# RPI_HAT_AMP_TAS5756_01.net
KiCad netlist of a schematic drawn in Altium Designer
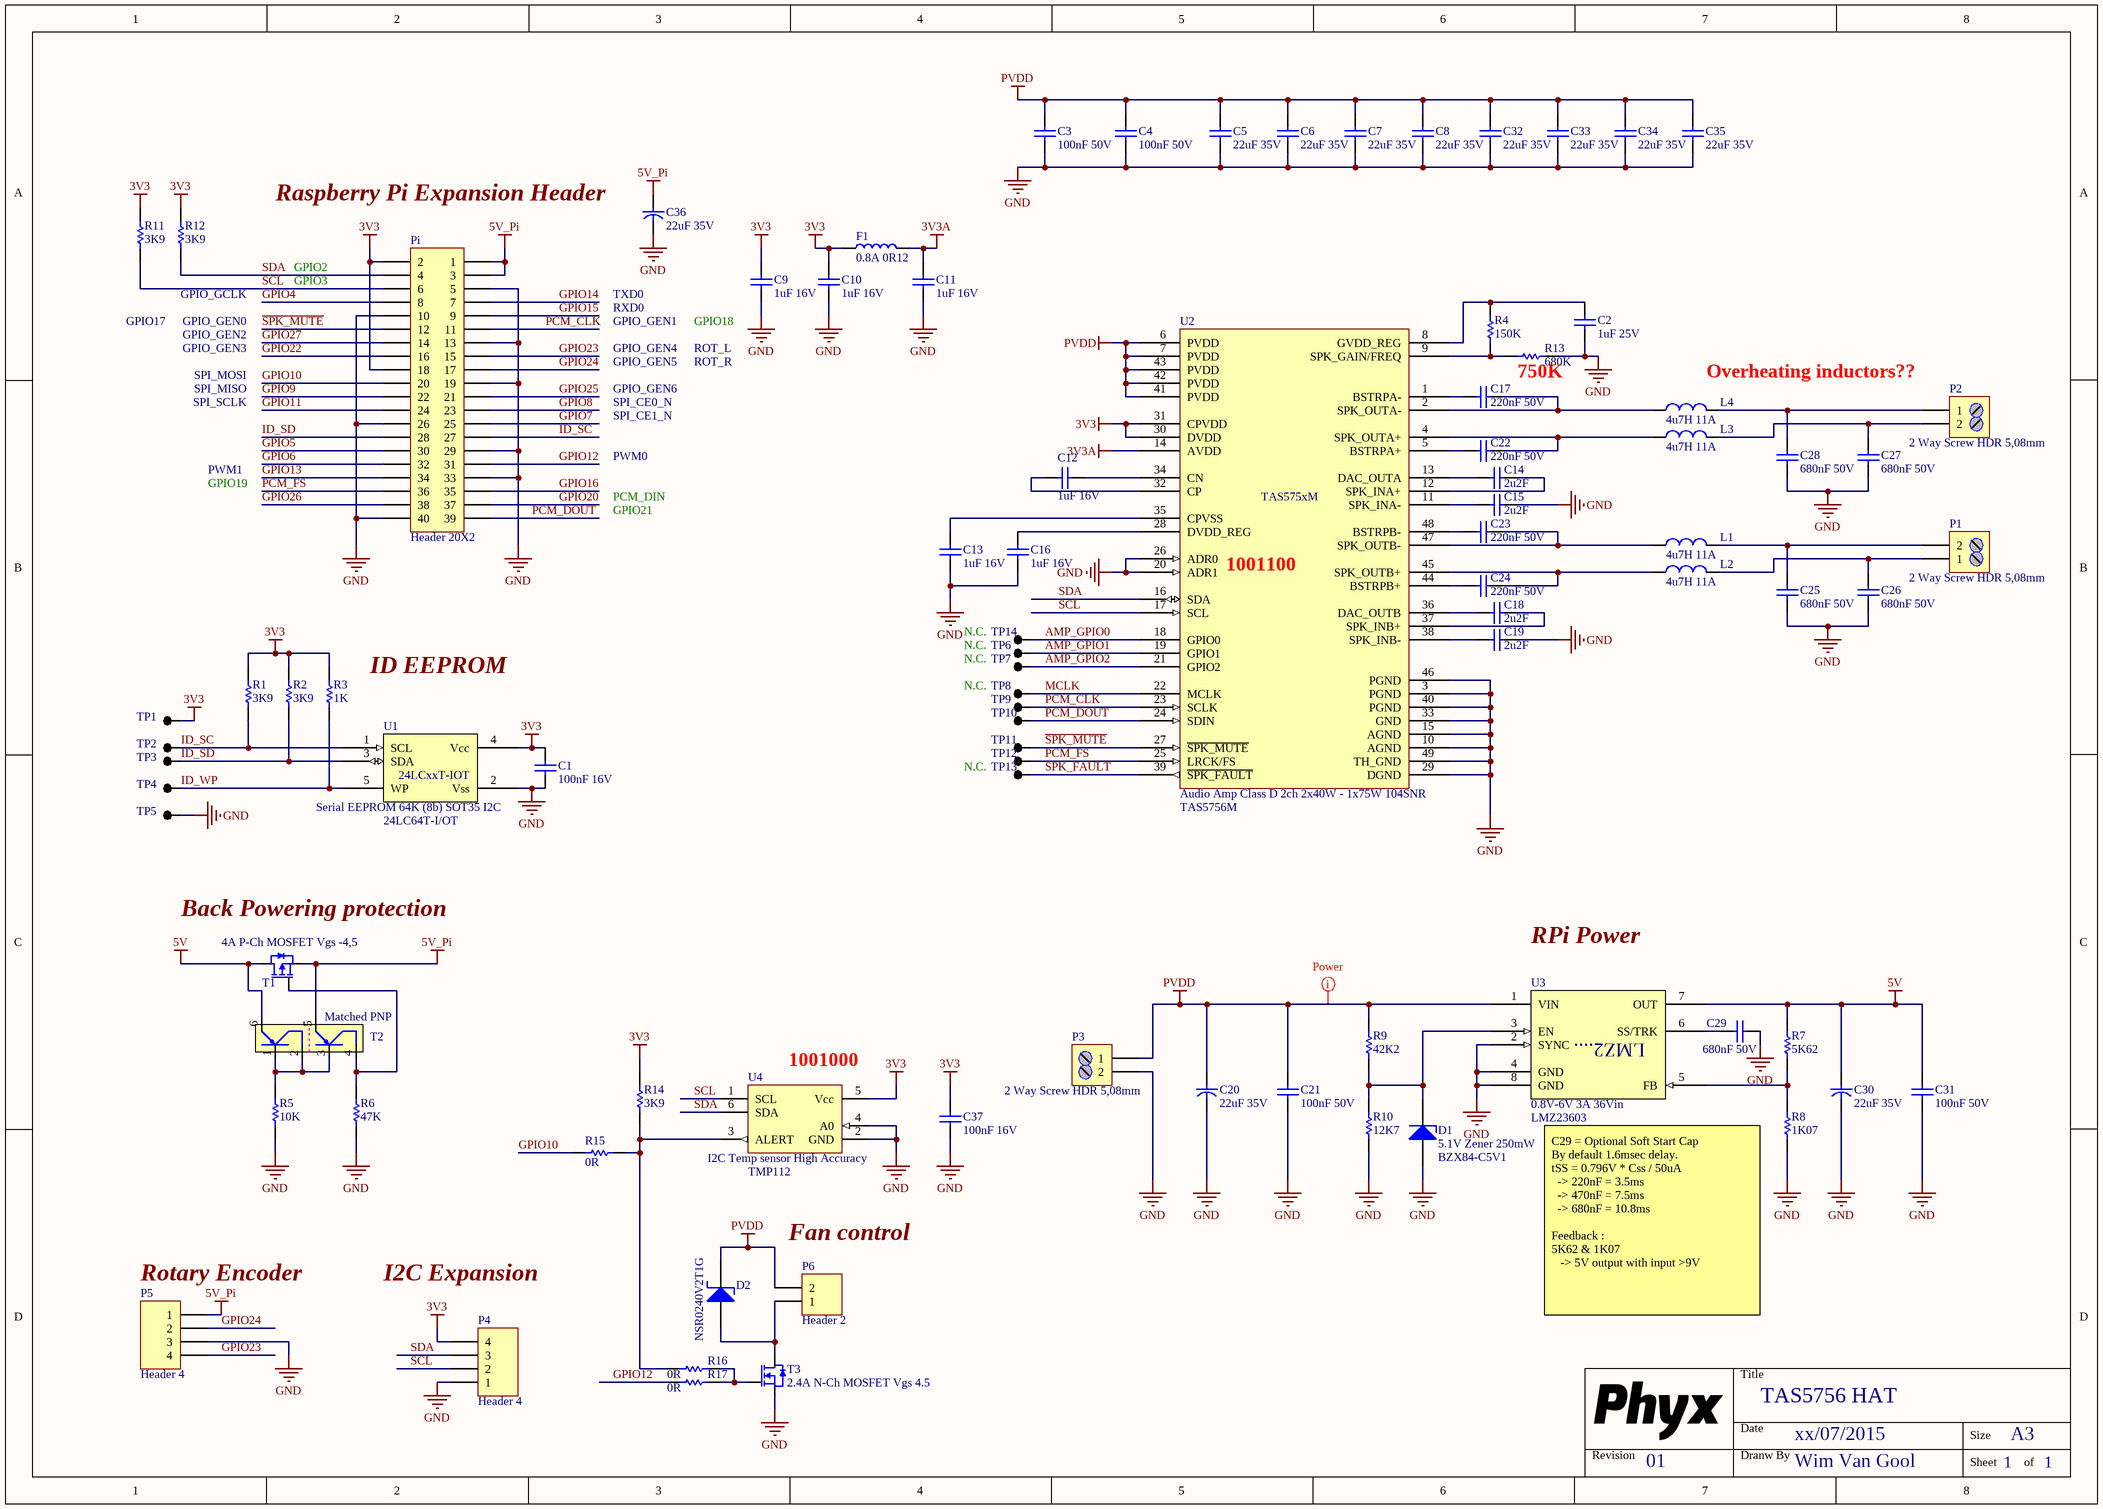
[diagram p0: RPI_HAT_AMP_TAS5756_01.SchDoc]

(export (version "E")
  (design (tool "Eeschema 10.0.6"))
  (components
    (comp (ref "C1")
      (value "100nF 16V")
      (footprint "C0603")
      (description "Capacitor Ceramic")
      (fields (field (name "Comment") "CAP_CERAMIC"))
      (libsource (lib "Phyx_Components") (part "CAP_CERAMIC"))
    )
    (comp (ref "C2")
      (value "1uF 25V")
      (footprint "C0805")
      (description "Capacitor Ceramic")
      (fields (field (name "Comment") "CAP_CERAMIC"))
      (libsource (lib "Phyx_Components") (part "CAP_CERAMIC"))
    )
    (comp (ref "C3")
      (value "100nF 50V")
      (footprint "C0805")
      (description "Capacitor Ceramic")
      (fields (field (name "Comment") "CAP_CERAMIC"))
      (libsource (lib "Phyx_Components") (part "CAP_CERAMIC"))
    )
    (comp (ref "C4")
      (value "100nF 50V")
      (footprint "C0805")
      (description "Capacitor Ceramic")
      (fields (field (name "Comment") "CAP_CERAMIC"))
      (libsource (lib "Phyx_Components") (part "CAP_CERAMIC"))
    )
    (comp (ref "C5")
      (value "22uF 35V")
      (footprint "C1206")
      (description "Capacitor Ceramic")
      (fields (field (name "Comment") "CAP_CERAMIC"))
      (libsource (lib "Phyx_Components") (part "CAP_CERAMIC"))
    )
    (comp (ref "C6")
      (value "22uF 35V")
      (footprint "C1206")
      (description "Capacitor Ceramic")
      (fields (field (name "Comment") "CAP_CERAMIC"))
      (libsource (lib "Phyx_Components") (part "CAP_CERAMIC"))
    )
    (comp (ref "C7")
      (value "22uF 35V")
      (footprint "C1206")
      (description "Capacitor Ceramic")
      (fields (field (name "Comment") "CAP_CERAMIC"))
      (libsource (lib "Phyx_Components") (part "CAP_CERAMIC"))
    )
    (comp (ref "C8")
      (value "22uF 35V")
      (footprint "C1206")
      (description "Capacitor Ceramic")
      (fields (field (name "Comment") "CAP_CERAMIC"))
      (libsource (lib "Phyx_Components") (part "CAP_CERAMIC"))
    )
    (comp (ref "C9")
      (value "1uF 16V")
      (footprint "C0603")
      (description "Capacitor Ceramic")
      (fields (field (name "Comment") "CAP_CERAMIC"))
      (libsource (lib "Phyx_Components") (part "CAP_CERAMIC"))
    )
    (comp (ref "C10")
      (value "1uF 16V")
      (footprint "C0603")
      (description "Capacitor Ceramic")
      (fields (field (name "Comment") "CAP_CERAMIC"))
      (libsource (lib "Phyx_Components") (part "CAP_CERAMIC"))
    )
    (comp (ref "C11")
      (value "1uF 16V")
      (footprint "C0603")
      (description "Capacitor Ceramic")
      (fields (field (name "Comment") "CAP_CERAMIC"))
      (libsource (lib "Phyx_Components") (part "CAP_CERAMIC"))
    )
    (comp (ref "C12")
      (value "1uF 16V")
      (footprint "C0603")
      (description "Capacitor Ceramic")
      (fields (field (name "Comment") "CAP_CERAMIC"))
      (libsource (lib "Phyx_Components") (part "CAP_CERAMIC"))
    )
    (comp (ref "C13")
      (value "1uF 16V")
      (footprint "C0603")
      (description "Capacitor Ceramic")
      (fields (field (name "Comment") "CAP_CERAMIC"))
      (libsource (lib "Phyx_Components") (part "CAP_CERAMIC"))
    )
    (comp (ref "C14")
      (value "2u2F")
      (footprint "C0805")
      (description "Capacitor Ceramic")
      (fields (field (name "Comment") "CAP_CERAMIC"))
      (libsource (lib "Phyx_Components") (part "CAP_CERAMIC"))
    )
    (comp (ref "C15")
      (value "2u2F")
      (footprint "C0805")
      (description "Capacitor Ceramic")
      (fields (field (name "Comment") "CAP_CERAMIC"))
      (libsource (lib "Phyx_Components") (part "CAP_CERAMIC"))
    )
    (comp (ref "C16")
      (value "1uF 16V")
      (footprint "C0603")
      (description "Capacitor Ceramic")
      (fields (field (name "Comment") "CAP_CERAMIC"))
      (libsource (lib "Phyx_Components") (part "CAP_CERAMIC"))
    )
    (comp (ref "C17")
      (value "220nF 50V")
      (footprint "C0805")
      (description "Capacitor Ceramic")
      (fields (field (name "Comment") "CAP_CERAMIC"))
      (libsource (lib "Phyx_Components") (part "CAP_CERAMIC"))
    )
    (comp (ref "C18")
      (value "2u2F")
      (footprint "C0805")
      (description "Capacitor Ceramic")
      (fields (field (name "Comment") "CAP_CERAMIC"))
      (libsource (lib "Phyx_Components") (part "CAP_CERAMIC"))
    )
    (comp (ref "C19")
      (value "2u2F")
      (footprint "C0805")
      (description "Capacitor Ceramic")
      (fields (field (name "Comment") "CAP_CERAMIC"))
      (libsource (lib "Phyx_Components") (part "CAP_CERAMIC"))
    )
    (comp (ref "C20")
      (value "22uF 35V")
      (footprint "C6.6x5.4")
      (description "Capacitor electrolyt")
      (fields (field (name "Comment") "CAP_POL"))
      (libsource (lib "Phyx_Components") (part "CAP_POL"))
    )
    (comp (ref "C21")
      (value "100nF 50V")
      (footprint "C0805")
      (description "Capacitor Ceramic")
      (fields (field (name "Comment") "CAP_CERAMIC"))
      (libsource (lib "Phyx_Components") (part "CAP_CERAMIC"))
    )
    (comp (ref "C22")
      (value "220nF 50V")
      (footprint "C0805")
      (description "Capacitor Ceramic")
      (fields (field (name "Comment") "CAP_CERAMIC"))
      (libsource (lib "Phyx_Components") (part "CAP_CERAMIC"))
    )
    (comp (ref "C23")
      (value "220nF 50V")
      (footprint "C0805")
      (description "Capacitor Ceramic")
      (fields (field (name "Comment") "CAP_CERAMIC"))
      (libsource (lib "Phyx_Components") (part "CAP_CERAMIC"))
    )
    (comp (ref "C24")
      (value "220nF 50V")
      (footprint "C0805")
      (description "Capacitor Ceramic")
      (fields (field (name "Comment") "CAP_CERAMIC"))
      (libsource (lib "Phyx_Components") (part "CAP_CERAMIC"))
    )
    (comp (ref "C25")
      (value "680nF 50V")
      (footprint "C0805")
      (description "Capacitor Ceramic")
      (fields (field (name "Comment") "CAP_CERAMIC"))
      (libsource (lib "Phyx_Components") (part "CAP_CERAMIC"))
    )
    (comp (ref "C26")
      (value "680nF 50V")
      (footprint "C0805")
      (description "Capacitor Ceramic")
      (fields (field (name "Comment") "CAP_CERAMIC"))
      (libsource (lib "Phyx_Components") (part "CAP_CERAMIC"))
    )
    (comp (ref "C27")
      (value "680nF 50V")
      (footprint "C0805")
      (description "Capacitor Ceramic")
      (fields (field (name "Comment") "CAP_CERAMIC"))
      (libsource (lib "Phyx_Components") (part "CAP_CERAMIC"))
    )
    (comp (ref "C28")
      (value "680nF 50V")
      (footprint "C0805")
      (description "Capacitor Ceramic")
      (fields (field (name "Comment") "CAP_CERAMIC"))
      (libsource (lib "Phyx_Components") (part "CAP_CERAMIC"))
    )
    (comp (ref "C29")
      (value "680nF 50V")
      (footprint "C0805")
      (description "Capacitor Ceramic")
      (fields (field (name "Comment") "CAP_CERAMIC"))
      (libsource (lib "Phyx_Components") (part "CAP_CERAMIC"))
    )
    (comp (ref "C30")
      (value "22uF 35V")
      (footprint "C6.6x5.4")
      (description "Capacitor electrolyt")
      (fields (field (name "Comment") "CAP_POL"))
      (libsource (lib "Phyx_Components") (part "CAP_POL"))
    )
    (comp (ref "C31")
      (value "100nF 50V")
      (footprint "C0805")
      (description "Capacitor Ceramic")
      (fields (field (name "Comment") "CAP_CERAMIC"))
      (libsource (lib "Phyx_Components") (part "CAP_CERAMIC"))
    )
    (comp (ref "C32")
      (value "22uF 35V")
      (footprint "C1206")
      (description "Capacitor Ceramic")
      (fields (field (name "Comment") "CAP_CERAMIC"))
      (libsource (lib "Phyx_Components") (part "CAP_CERAMIC"))
    )
    (comp (ref "C33")
      (value "22uF 35V")
      (footprint "C1206")
      (description "Capacitor Ceramic")
      (fields (field (name "Comment") "CAP_CERAMIC"))
      (libsource (lib "Phyx_Components") (part "CAP_CERAMIC"))
    )
    (comp (ref "C34")
      (value "22uF 35V")
      (footprint "C1206")
      (description "Capacitor Ceramic")
      (fields (field (name "Comment") "CAP_CERAMIC"))
      (libsource (lib "Phyx_Components") (part "CAP_CERAMIC"))
    )
    (comp (ref "C35")
      (value "22uF 35V")
      (footprint "C1206")
      (description "Capacitor Ceramic")
      (fields (field (name "Comment") "CAP_CERAMIC"))
      (libsource (lib "Phyx_Components") (part "CAP_CERAMIC"))
    )
    (comp (ref "C36")
      (value "22uF 35V")
      (footprint "C6.6x5.4")
      (description "Capacitor electrolyt")
      (fields (field (name "Comment") "CAP_POL"))
      (libsource (lib "Phyx_Components") (part "CAP_POL"))
    )
    (comp (ref "C37")
      (value "100nF 16V")
      (footprint "C0603")
      (description "Capacitor Ceramic")
      (fields (field (name "Comment") "CAP_CERAMIC"))
      (libsource (lib "Phyx_Components") (part "CAP_CERAMIC"))
    )
    (comp (ref "D1")
      (value "5.1V Zener 250mW")
      (footprint "SOT23-3")
      (description "Default Diode")
      (fields (field (name "ALTIUM_VALUE") "BZX84-C5V1"))
      (libsource (lib "Phyx_Components") (part "Zener_BZX84"))
    )
    (comp (ref "D2")
      (value "NSR0240V2T1G")
      (footprint "ON_SOD-523")
      (description "Schottky NSR0240V2T1G")
      (fields (field (name "Comment") "NSR0240V2T1G Schottky ULTRAFAST, 200MA, 40V"))
      (libsource (lib "Phyx_Components") (part "Schottky_CA"))
    )
    (comp (ref "F1")
      (value "0.8A 0R12")
      (footprint "L0805")
      (fields (field (name "Comment") "FERRITE"))
      (libsource (lib "Phyx_Components") (part "FERRITE"))
    )
    (comp (ref "L1")
      (value "4u7H 11A")
      (footprint "XAL6060-472")
      (fields (field (name "Comment") "XAL6060-472MEC"))
      (libsource (lib "Phyx_Components") (part "INDUCTOR"))
    )
    (comp (ref "L2")
      (value "4u7H 11A")
      (footprint "XAL6060-472")
      (fields (field (name "Comment") "XAL6060-472MEC"))
      (libsource (lib "Phyx_Components") (part "INDUCTOR"))
    )
    (comp (ref "L3")
      (value "4u7H 11A")
      (footprint "XAL6060-472")
      (fields (field (name "Comment") "XAL6060-472MEC"))
      (libsource (lib "Phyx_Components") (part "INDUCTOR"))
    )
    (comp (ref "L4")
      (value "4u7H 11A")
      (footprint "XAL6060-472")
      (fields (field (name "Comment") "XAL6060-472MEC"))
      (libsource (lib "Phyx_Components") (part "INDUCTOR"))
    )
    (comp (ref "P1")
      (value "2 Way Screw HDR 5,08mm")
      (footprint "TERM_BLK-0508-2-90")
      (libsource (lib "Phyx_Components") (part "TERM_BLCK_2"))
    )
    (comp (ref "P2")
      (value "2 Way Screw HDR 5,08mm")
      (footprint "TERM_BLK-0508-2-90")
      (libsource (lib "") (part "TERM_BLCK_2_2"))
    )
    (comp (ref "P3")
      (value "2 Way Screw HDR 5,08mm")
      (footprint "TERM_BLK-0508-2-90")
      (libsource (lib "") (part "TERM_BLCK_2_1"))
    )
    (comp (ref "P4")
      (value "Header 4")
      (footprint "HDR1X4")
      (libsource (lib "Phyx_Components") (part "Header 4"))
    )
    (comp (ref "P5") (value "Header 4") (footprint "HDR1X4") (libsource (lib "") (part "Header 4_1")))
    (comp (ref "P6")
      (value "Header 2")
      (footprint "HDR1X2")
      (description "Pin Header 2.54mm 2way")
      (libsource (lib "Phyx_Components") (part "Header 2"))
    )
    (comp (ref "Pi")
      (value "Header 20X2")
      (footprint "RCPT2X20")
      (description "=Description")
      (libsource (lib "Phyx_Components") (part "Header 20X2"))
    )
    (comp (ref "R1")
      (value "3K9")
      (footprint "R0603")
      (fields (field (name "Comment") "RESISTOR"))
      (libsource (lib "Phyx_Components") (part "RESISTOR"))
    )
    (comp (ref "R2")
      (value "3K9")
      (footprint "R0603")
      (fields (field (name "Comment") "RESISTOR"))
      (libsource (lib "Phyx_Components") (part "RESISTOR"))
    )
    (comp (ref "R3")
      (value "1K")
      (footprint "R0603")
      (fields (field (name "Comment") "RESISTOR"))
      (libsource (lib "Phyx_Components") (part "RESISTOR"))
    )
    (comp (ref "R4")
      (value "150K")
      (footprint "R0603")
      (fields (field (name "Comment") "RESISTOR"))
      (libsource (lib "Phyx_Components") (part "RESISTOR"))
    )
    (comp (ref "R5")
      (value "10K")
      (footprint "R0603")
      (fields (field (name "Comment") "RESISTOR"))
      (libsource (lib "Phyx_Components") (part "RESISTOR"))
    )
    (comp (ref "R6")
      (value "47K")
      (footprint "R0603")
      (fields (field (name "Comment") "RESISTOR"))
      (libsource (lib "Phyx_Components") (part "RESISTOR"))
    )
    (comp (ref "R7")
      (value "5K62")
      (footprint "R0603")
      (fields (field (name "Comment") "RESISTOR"))
      (libsource (lib "Phyx_Components") (part "RESISTOR"))
    )
    (comp (ref "R8")
      (value "1K07")
      (footprint "R0603")
      (fields (field (name "Comment") "RESISTOR"))
      (libsource (lib "Phyx_Components") (part "RESISTOR"))
    )
    (comp (ref "R9")
      (value "42K2")
      (footprint "R0603")
      (fields (field (name "Comment") "RESISTOR"))
      (libsource (lib "Phyx_Components") (part "RESISTOR"))
    )
    (comp (ref "R10")
      (value "12K7")
      (footprint "R0603")
      (fields (field (name "Comment") "RESISTOR"))
      (libsource (lib "Phyx_Components") (part "RESISTOR"))
    )
    (comp (ref "R11")
      (value "3K9")
      (footprint "R0603")
      (fields (field (name "Comment") "RESISTOR"))
      (libsource (lib "Phyx_Components") (part "RESISTOR"))
    )
    (comp (ref "R12")
      (value "3K9")
      (footprint "R0603")
      (fields (field (name "Comment") "RESISTOR"))
      (libsource (lib "Phyx_Components") (part "RESISTOR"))
    )
    (comp (ref "R13")
      (value "680K")
      (footprint "R0603")
      (fields (field (name "Comment") "RESISTOR"))
      (libsource (lib "Phyx_Components") (part "RESISTOR"))
    )
    (comp (ref "R14")
      (value "3K9")
      (footprint "R0603")
      (fields (field (name "Comment") "RESISTOR"))
      (libsource (lib "Phyx_Components") (part "RESISTOR"))
    )
    (comp (ref "R15")
      (value "0R")
      (footprint "R0603")
      (description "RES # 0R 0603")
      (fields (field (name "Comment") "RESISTOR"))
      (libsource (lib "Phyx_Components") (part "RESISTOR"))
    )
    (comp (ref "R16")
      (value "0R")
      (footprint "R0603")
      (description "RES # 0R 0603")
      (fields (field (name "Comment") "RESISTOR"))
      (libsource (lib "Phyx_Components") (part "RESISTOR"))
    )
    (comp (ref "R17")
      (value "0R")
      (footprint "R0603")
      (description "RES # 0R 0603")
      (fields (field (name "Comment") "RESISTOR"))
      (libsource (lib "Phyx_Components") (part "RESISTOR"))
    )
    (comp (ref "T1")
      (value "4A P-Ch MOSFET Vgs -4,5")
      (footprint "SOT23-3")
      (description "=Description")
      (libsource (lib "Phyx_Components") (part "P_MOSFET_GSD"))
    )
    (comp (ref "T2")
      (value "Matched PNP")
      (footprint "SOT23-6")
      (libsource (lib "Phyx_Components") (part "DMMT5401"))
    )
    (comp (ref "T3")
      (value "2.4A N-Ch MOSFET Vgs 4.5")
      (footprint "SOT23-3")
      (description "ZXMN2B01F N-Ch MOSFET 2.4A 4.5Vgs 30Vds")
      (libsource (lib "Phyx_Components") (part "N_MOSFET_GSD"))
    )
    (comp (ref "TP1")
      (value "TEST_PAD")
      (footprint "TP_1.2mm_0.6mm")
      (libsource (lib "Phyx_Components") (part "TEST_PAD"))
    )
    (comp (ref "TP2")
      (value "TEST_PAD")
      (footprint "TP_1.2mm_0.6mm")
      (libsource (lib "Phyx_Components") (part "TEST_PAD"))
    )
    (comp (ref "TP3")
      (value "TEST_PAD")
      (footprint "TP_1.2mm_0.6mm")
      (libsource (lib "Phyx_Components") (part "TEST_PAD"))
    )
    (comp (ref "TP4")
      (value "TEST_PAD")
      (footprint "TP_1.2mm_0.6mm")
      (libsource (lib "Phyx_Components") (part "TEST_PAD"))
    )
    (comp (ref "TP5")
      (value "TEST_PAD")
      (footprint "TP_1.2mm_0.6mm")
      (libsource (lib "Phyx_Components") (part "TEST_PAD"))
    )
    (comp (ref "TP6")
      (value "TEST_PAD")
      (footprint "TP_0.4mm")
      (libsource (lib "Phyx_Components") (part "TEST_PAD"))
    )
    (comp (ref "TP7")
      (value "TEST_PAD")
      (footprint "TP_0.4mm")
      (libsource (lib "Phyx_Components") (part "TEST_PAD"))
    )
    (comp (ref "TP8")
      (value "TEST_PAD")
      (footprint "TP_0.4mm")
      (libsource (lib "Phyx_Components") (part "TEST_PAD"))
    )
    (comp (ref "TP9")
      (value "TEST_PAD")
      (footprint "TP_0.4mm")
      (libsource (lib "Phyx_Components") (part "TEST_PAD"))
    )
    (comp (ref "TP10")
      (value "TEST_PAD")
      (footprint "TP_0.4mm")
      (libsource (lib "Phyx_Components") (part "TEST_PAD"))
    )
    (comp (ref "TP11")
      (value "TEST_PAD")
      (footprint "TP_0.4mm")
      (libsource (lib "Phyx_Components") (part "TEST_PAD"))
    )
    (comp (ref "TP12")
      (value "TEST_PAD")
      (footprint "TP_0.4mm")
      (libsource (lib "Phyx_Components") (part "TEST_PAD"))
    )
    (comp (ref "TP13")
      (value "TEST_PAD")
      (footprint "TP_0.4mm")
      (libsource (lib "Phyx_Components") (part "TEST_PAD"))
    )
    (comp (ref "TP14")
      (value "TEST_PAD")
      (footprint "TP_0.4mm")
      (libsource (lib "Phyx_Components") (part "TEST_PAD"))
    )
    (comp (ref "U1")
      (value "Serial EEPROM 64K (8b) SOT35 I2C")
      (footprint "SOT23-5")
      (description "=Description")
      (fields (field (name "ALTIUM_VALUE") "24LC64T-I/OT"))
      (libsource (lib "Phyx_Components") (part "24LCxxT-IOT"))
    )
    (comp (ref "U2")
      (value "Audio Amp Class D 2ch 2x40W - 1x75W 104SNR")
      (footprint "TI-DCA-R-PDSO-G48")
      (description "=Description")
      (fields (field (name "ALTIUM_VALUE") "TAS5756M"))
      (libsource (lib "Phyx_Components") (part "TAS575xM"))
    )
    (comp (ref "U3")
      (value "0.8V-6V 3A 36Vin")
      (footprint "7TO-PMOD")
      (description "=Description")
      (fields (field (name "ALTIUM_VALUE") "LMZ23603"))
      (libsource (lib "Phyx_Components") (part "LMZ2_7pin"))
    )
    (comp (ref "U4")
      (value "I2C Temp sensor High Accuracy")
      (footprint "TI_DRL_R-PDSO-N6")
      (description "TEMP # TMP112")
      (fields (field (name "ALTIUM_VALUE") "TMP112"))
      (libsource (lib "Phyx_Components") (part "TMP1x2"))
    )
  )
  (nets
    (net (code "1") (name "/AMP_GPIO0") (class "Default")
      (node (ref "TP14") (pin "1") (pinfunction "1_1") (pintype "passive"))
      (node (ref "U2") (pin "18") (pinfunction "GPIO0_18") (pintype "passive"))
    )
    (net (code "2") (name "/AMP_GPIO1") (class "Default")
      (node (ref "TP6") (pin "1") (pinfunction "1_1") (pintype "passive"))
      (node (ref "U2") (pin "19") (pinfunction "GPIO1_19") (pintype "passive"))
    )
    (net (code "3") (name "/AMP_GPIO2") (class "Default")
      (node (ref "TP7") (pin "1") (pinfunction "1_1") (pintype "passive"))
      (node (ref "U2") (pin "21") (pinfunction "GPIO2_21") (pintype "passive"))
    )
    (net (code "4") (name "/GPIO4") (class "Default")
      (node (ref "Pi") (pin "8") (pinfunction "8_8") (pintype "passive"))
    )
    (net (code "5") (name "/GPIO5") (class "Default")
      (node (ref "Pi") (pin "30") (pinfunction "30_30") (pintype "passive"))
    )
    (net (code "6") (name "/GPIO6") (class "Default")
      (node (ref "Pi") (pin "32") (pinfunction "32_32") (pintype "passive"))
    )
    (net (code "7") (name "/GPIO7") (class "Default")
      (node (ref "Pi") (pin "25") (pinfunction "25_25") (pintype "passive"))
    )
    (net (code "8") (name "/GPIO8") (class "Default")
      (node (ref "Pi") (pin "23") (pinfunction "23_23") (pintype "passive"))
    )
    (net (code "9") (name "/GPIO9") (class "Default")
      (node (ref "Pi") (pin "22") (pinfunction "22_22") (pintype "passive"))
    )
    (net (code "10") (name "/GPIO10") (class "Default")
      (node (ref "Pi") (pin "20") (pinfunction "20_20") (pintype "passive"))
      (node (ref "R15") (pin "1") (pinfunction "1_1") (pintype "passive"))
    )
    (net (code "11") (name "/GPIO11") (class "Default")
      (node (ref "Pi") (pin "24") (pinfunction "24_24") (pintype "passive"))
    )
    (net (code "12") (name "/GPIO12") (class "Default")
      (node (ref "Pi") (pin "31") (pinfunction "31_31") (pintype "passive"))
      (node (ref "R17") (pin "2") (pinfunction "2_2") (pintype "passive"))
    )
    (net (code "13") (name "/GPIO13") (class "Default")
      (node (ref "Pi") (pin "34") (pinfunction "34_34") (pintype "passive"))
    )
    (net (code "14") (name "/GPIO14") (class "Default")
      (node (ref "Pi") (pin "7") (pinfunction "7_7") (pintype "passive"))
    )
    (net (code "15") (name "/GPIO15") (class "Default")
      (node (ref "Pi") (pin "9") (pinfunction "9_9") (pintype "passive"))
    )
    (net (code "16") (name "/GPIO16") (class "Default")
      (node (ref "Pi") (pin "35") (pinfunction "35_35") (pintype "passive"))
    )
    (net (code "17") (name "/GPIO20") (class "Default")
      (node (ref "Pi") (pin "37") (pinfunction "37_37") (pintype "passive"))
    )
    (net (code "18") (name "/GPIO22") (class "Default")
      (node (ref "Pi") (pin "16") (pinfunction "16_16") (pintype "passive"))
    )
    (net (code "19") (name "/GPIO23") (class "Default")
      (node (ref "P5") (pin "4") (pinfunction "4_4") (pintype "passive"))
      (node (ref "Pi") (pin "15") (pinfunction "15_15") (pintype "passive"))
    )
    (net (code "20") (name "/GPIO24") (class "Default")
      (node (ref "P5") (pin "2") (pinfunction "2_2") (pintype "passive"))
      (node (ref "Pi") (pin "17") (pinfunction "17_17") (pintype "passive"))
    )
    (net (code "21") (name "/GPIO25") (class "Default")
      (node (ref "Pi") (pin "21") (pinfunction "21_21") (pintype "passive"))
    )
    (net (code "22") (name "/GPIO26") (class "Default")
      (node (ref "Pi") (pin "38") (pinfunction "38_38") (pintype "passive"))
    )
    (net (code "23") (name "/GPIO27") (class "Default")
      (node (ref "Pi") (pin "14") (pinfunction "14_14") (pintype "passive"))
    )
    (net (code "24") (name "/ID_SC") (class "Default")
      (node (ref "Pi") (pin "27") (pinfunction "27_27") (pintype "passive"))
      (node (ref "R1") (pin "2") (pinfunction "2_2") (pintype "passive"))
      (node (ref "TP2") (pin "1") (pinfunction "1_1") (pintype "passive"))
      (node (ref "U1") (pin "1") (pinfunction "SCL_1") (pintype "input"))
    )
    (net (code "25") (name "/ID_SD") (class "Default")
      (node (ref "Pi") (pin "28") (pinfunction "28_28") (pintype "passive"))
      (node (ref "R2") (pin "2") (pinfunction "2_2") (pintype "passive"))
      (node (ref "TP3") (pin "1") (pinfunction "1_1") (pintype "passive"))
      (node (ref "U1") (pin "3") (pinfunction "SDA_3") (pintype "bidirectional"))
    )
    (net (code "26") (name "/ID_WP") (class "Default")
      (node (ref "R3") (pin "2") (pinfunction "2_2") (pintype "passive"))
      (node (ref "TP4") (pin "1") (pinfunction "1_1") (pintype "passive"))
      (node (ref "U1") (pin "5") (pinfunction "WP_5") (pintype "passive"))
    )
    (net (code "27") (name "/MCLK") (class "Default")
      (node (ref "TP8") (pin "1") (pinfunction "1_1") (pintype "passive"))
      (node (ref "U2") (pin "22") (pinfunction "MCLK_22") (pintype "passive"))
    )
    (net (code "28") (name "/PCM_CLK") (class "Default")
      (node (ref "Pi") (pin "11") (pinfunction "11_11") (pintype "passive"))
      (node (ref "TP9") (pin "1") (pinfunction "1_1") (pintype "passive"))
      (node (ref "U2") (pin "23") (pinfunction "SCLK_23") (pintype "input"))
    )
    (net (code "29") (name "/PCM_DOUT") (class "Default")
      (node (ref "Pi") (pin "39") (pinfunction "39_39") (pintype "passive"))
      (node (ref "TP10") (pin "1") (pinfunction "1_1") (pintype "passive"))
      (node (ref "U2") (pin "24") (pinfunction "SDIN_24") (pintype "input"))
    )
    (net (code "30") (name "/PCM_FS") (class "Default")
      (node (ref "Pi") (pin "36") (pinfunction "36_36") (pintype "passive"))
      (node (ref "TP12") (pin "1") (pinfunction "1_1") (pintype "passive"))
      (node (ref "U2") (pin "25") (pinfunction "LRCK/FS_25") (pintype "input"))
    )
    (net (code "31") (name "/SCL") (class "Default")
      (node (ref "P4") (pin "2") (pinfunction "2_2") (pintype "passive"))
      (node (ref "Pi") (pin "6") (pinfunction "6_6") (pintype "passive"))
      (node (ref "R11") (pin "2") (pinfunction "2_2") (pintype "passive"))
      (node (ref "U2") (pin "17") (pinfunction "SCL_17") (pintype "input"))
      (node (ref "U4") (pin "1") (pinfunction "SCL_1") (pintype "open_collector"))
    )
    (net (code "32") (name "/SDA") (class "Default")
      (node (ref "P4") (pin "3") (pinfunction "3_3") (pintype "passive"))
      (node (ref "Pi") (pin "4") (pinfunction "4_4") (pintype "passive"))
      (node (ref "R12") (pin "2") (pinfunction "2_2") (pintype "passive"))
      (node (ref "U2") (pin "16") (pinfunction "SDA_16") (pintype "bidirectional"))
      (node (ref "U4") (pin "6") (pinfunction "SDA_6") (pintype "open_collector"))
    )
    (net (code "33") (name "/~{SPK_FAULT}") (class "Default")
      (node (ref "TP13") (pin "1") (pinfunction "1_1") (pintype "passive"))
      (node (ref "U2") (pin "39") (pinfunction "~{SPK_FAULT}_39") (pintype "output"))
    )
    (net (code "34") (name "/~{SPK_MUTE}") (class "Default")
      (node (ref "Pi") (pin "12") (pinfunction "12_12") (pintype "passive"))
      (node (ref "TP11") (pin "1") (pinfunction "1_1") (pintype "passive"))
      (node (ref "U2") (pin "27") (pinfunction "~{SPK_MUTE}_27") (pintype "input"))
    )
    (net (code "35") (name "3V3") (class "Default")
      (node (ref "C1") (pin "1") (pinfunction "1_1") (pintype "passive"))
      (node (ref "C10") (pin "1") (pinfunction "1_1") (pintype "passive"))
      (node (ref "C37") (pin "1") (pinfunction "1_1") (pintype "passive"))
      (node (ref "C9") (pin "1") (pinfunction "1_1") (pintype "passive"))
      (node (ref "F1") (pin "1") (pinfunction "1_1") (pintype "passive"))
      (node (ref "P4") (pin "4") (pinfunction "4_4") (pintype "passive"))
      (node (ref "Pi") (pin "18") (pinfunction "18_18") (pintype "passive"))
      (node (ref "Pi") (pin "2") (pinfunction "2_2") (pintype "passive"))
      (node (ref "R1") (pin "1") (pinfunction "1_1") (pintype "passive"))
      (node (ref "R11") (pin "1") (pinfunction "1_1") (pintype "passive"))
      (node (ref "R12") (pin "1") (pinfunction "1_1") (pintype "passive"))
      (node (ref "R14") (pin "1") (pinfunction "1_1") (pintype "passive"))
      (node (ref "R2") (pin "1") (pinfunction "1_1") (pintype "passive"))
      (node (ref "R3") (pin "1") (pinfunction "1_1") (pintype "passive"))
      (node (ref "TP1") (pin "1") (pinfunction "1_1") (pintype "passive"))
      (node (ref "U1") (pin "4") (pinfunction "Vcc_4") (pintype "passive"))
      (node (ref "U2") (pin "30") (pinfunction "DVDD_30") (pintype "power_in"))
      (node (ref "U2") (pin "31") (pinfunction "CPVDD_31") (pintype "passive"))
      (node (ref "U4") (pin "5") (pinfunction "Vcc_5") (pintype "power_in"))
    )
    (net (code "36") (name "3V3A") (class "Default")
      (node (ref "C11") (pin "1") (pinfunction "1_1") (pintype "passive"))
      (node (ref "F1") (pin "2") (pinfunction "2_2") (pintype "passive"))
      (node (ref "U2") (pin "14") (pinfunction "AVDD_14") (pintype "power_in"))
    )
    (net (code "37") (name "5V") (class "Default")
      (node (ref "C30") (pin "1") (pinfunction "1_1") (pintype "passive"))
      (node (ref "C31") (pin "1") (pinfunction "1_1") (pintype "passive"))
      (node (ref "R7") (pin "1") (pinfunction "1_1") (pintype "passive"))
      (node (ref "T1") (pin "3") (pinfunction "D_3") (pintype "passive"))
      (node (ref "T2") (pin "6") (pinfunction "E_6") (pintype "passive"))
      (node (ref "U3") (pin "7") (pinfunction "OUT_7") (pintype "power_in"))
    )
    (net (code "38") (name "5V_Pi") (class "Default")
      (node (ref "C36") (pin "1") (pinfunction "1_1") (pintype "passive"))
      (node (ref "P5") (pin "1") (pinfunction "1_1") (pintype "passive"))
      (node (ref "Pi") (pin "1") (pinfunction "1_1") (pintype "passive"))
      (node (ref "Pi") (pin "3") (pinfunction "3_3") (pintype "passive"))
      (node (ref "T1") (pin "2") (pinfunction "S_2") (pintype "passive"))
      (node (ref "T2") (pin "5") (pinfunction "E_5") (pintype "passive"))
    )
    (net (code "39") (name "GND") (class "Default")
      (node (ref "C1") (pin "2") (pinfunction "2_2") (pintype "passive"))
      (node (ref "C10") (pin "2") (pinfunction "2_2") (pintype "passive"))
      (node (ref "C11") (pin "2") (pinfunction "2_2") (pintype "passive"))
      (node (ref "C13") (pin "2") (pinfunction "2_2") (pintype "passive"))
      (node (ref "C15") (pin "1") (pinfunction "1_1") (pintype "passive"))
      (node (ref "C16") (pin "2") (pinfunction "2_2") (pintype "passive"))
      (node (ref "C19") (pin "1") (pinfunction "1_1") (pintype "passive"))
      (node (ref "C2") (pin "2") (pinfunction "2_2") (pintype "passive"))
      (node (ref "C20") (pin "2") (pinfunction "2_2") (pintype "passive"))
      (node (ref "C21") (pin "2") (pinfunction "2_2") (pintype "passive"))
      (node (ref "C25") (pin "1") (pinfunction "1_1") (pintype "passive"))
      (node (ref "C26") (pin "1") (pinfunction "1_1") (pintype "passive"))
      (node (ref "C27") (pin "1") (pinfunction "1_1") (pintype "passive"))
      (node (ref "C28") (pin "1") (pinfunction "1_1") (pintype "passive"))
      (node (ref "C29") (pin "1") (pinfunction "1_1") (pintype "passive"))
      (node (ref "C3") (pin "2") (pinfunction "2_2") (pintype "passive"))
      (node (ref "C30") (pin "2") (pinfunction "2_2") (pintype "passive"))
      (node (ref "C31") (pin "2") (pinfunction "2_2") (pintype "passive"))
      (node (ref "C32") (pin "2") (pinfunction "2_2") (pintype "passive"))
      (node (ref "C33") (pin "2") (pinfunction "2_2") (pintype "passive"))
      (node (ref "C34") (pin "2") (pinfunction "2_2") (pintype "passive"))
      (node (ref "C35") (pin "2") (pinfunction "2_2") (pintype "passive"))
      (node (ref "C36") (pin "2") (pinfunction "2_2") (pintype "passive"))
      (node (ref "C37") (pin "2") (pinfunction "2_2") (pintype "passive"))
      (node (ref "C4") (pin "2") (pinfunction "2_2") (pintype "passive"))
      (node (ref "C5") (pin "2") (pinfunction "2_2") (pintype "passive"))
      (node (ref "C6") (pin "2") (pinfunction "2_2") (pintype "passive"))
      (node (ref "C7") (pin "2") (pinfunction "2_2") (pintype "passive"))
      (node (ref "C8") (pin "2") (pinfunction "2_2") (pintype "passive"))
      (node (ref "C9") (pin "2") (pinfunction "2_2") (pintype "passive"))
      (node (ref "D1") (pin "1") (pinfunction "A_1") (pintype "passive"))
      (node (ref "P3") (pin "2") (pinfunction "2_2") (pintype "passive"))
      (node (ref "P4") (pin "1") (pinfunction "1_1") (pintype "passive"))
      (node (ref "P5") (pin "3") (pinfunction "3_3") (pintype "passive"))
      (node (ref "Pi") (pin "10") (pinfunction "10_10") (pintype "passive"))
      (node (ref "Pi") (pin "13") (pinfunction "13_13") (pintype "passive"))
      (node (ref "Pi") (pin "19") (pinfunction "19_19") (pintype "passive"))
      (node (ref "Pi") (pin "26") (pinfunction "26_26") (pintype "passive"))
      (node (ref "Pi") (pin "29") (pinfunction "29_29") (pintype "passive"))
      (node (ref "Pi") (pin "33") (pinfunction "33_33") (pintype "passive"))
      (node (ref "Pi") (pin "40") (pinfunction "40_40") (pintype "passive"))
      (node (ref "Pi") (pin "5") (pinfunction "5_5") (pintype "passive"))
      (node (ref "R10") (pin "1") (pinfunction "1_1") (pintype "passive"))
      (node (ref "R13") (pin "1") (pinfunction "1_1") (pintype "passive"))
      (node (ref "R5") (pin "2") (pinfunction "2_2") (pintype "passive"))
      (node (ref "R6") (pin "2") (pinfunction "2_2") (pintype "passive"))
      (node (ref "R8") (pin "2") (pinfunction "2_2") (pintype "passive"))
      (node (ref "T3") (pin "2") (pinfunction "S_2") (pintype "passive"))
      (node (ref "TP5") (pin "1") (pinfunction "1_1") (pintype "passive"))
      (node (ref "U1") (pin "2") (pinfunction "Vss_2") (pintype "passive"))
      (node (ref "U2") (pin "10") (pinfunction "AGND_10") (pintype "power_in"))
      (node (ref "U2") (pin "15") (pinfunction "AGND_15") (pintype "power_in"))
      (node (ref "U2") (pin "20") (pinfunction "ADR1_20") (pintype "input"))
      (node (ref "U2") (pin "26") (pinfunction "ADR0_26") (pintype "input"))
      (node (ref "U2") (pin "29") (pinfunction "DGND_29") (pintype "power_in"))
      (node (ref "U2") (pin "3") (pinfunction "PGND_3") (pintype "power_in"))
      (node (ref "U2") (pin "33") (pinfunction "GND_33") (pintype "power_in"))
      (node (ref "U2") (pin "40") (pinfunction "PGND_40") (pintype "power_in"))
      (node (ref "U2") (pin "46") (pinfunction "PGND_46") (pintype "power_in"))
      (node (ref "U2") (pin "49") (pinfunction "TH_GND_49") (pintype "passive"))
      (node (ref "U3") (pin "2") (pinfunction "SYNC_2") (pintype "input"))
      (node (ref "U3") (pin "4") (pinfunction "GND_4") (pintype "power_in"))
      (node (ref "U3") (pin "8") (pinfunction "GND_8") (pintype "power_in"))
      (node (ref "U4") (pin "2") (pinfunction "GND_2") (pintype "power_in"))
      (node (ref "U4") (pin "4") (pinfunction "A0_4") (pintype "input"))
    )
    (net (code "40") (name "Net-(C25-Pad2)") (class "Default")
      (node (ref "C25") (pin "2") (pinfunction "2_2") (pintype "passive"))
      (node (ref "L1") (pin "2") (pinfunction "2_2") (pintype "passive"))
      (node (ref "P1") (pin "2") (pinfunction "2_2") (pintype "passive"))
    )
    (net (code "41") (name "Net-(C26-Pad2)") (class "Default")
      (node (ref "C26") (pin "2") (pinfunction "2_2") (pintype "passive"))
      (node (ref "L2") (pin "2") (pinfunction "2_2") (pintype "passive"))
      (node (ref "P1") (pin "1") (pinfunction "1_1") (pintype "passive"))
    )
    (net (code "42") (name "Net-(C27-Pad2)") (class "Default")
      (node (ref "C27") (pin "2") (pinfunction "2_2") (pintype "passive"))
      (node (ref "L3") (pin "2") (pinfunction "2_2") (pintype "passive"))
      (node (ref "P2") (pin "2") (pinfunction "2_2") (pintype "passive"))
    )
    (net (code "43") (name "Net-(C28-Pad2)") (class "Default")
      (node (ref "C28") (pin "2") (pinfunction "2_2") (pintype "passive"))
      (node (ref "L4") (pin "2") (pinfunction "2_2") (pintype "passive"))
      (node (ref "P2") (pin "1") (pinfunction "1_1") (pintype "passive"))
    )
    (net (code "44") (name "Net-(D1-K)") (class "Default")
      (node (ref "D1") (pin "3") (pinfunction "K_3") (pintype "passive"))
      (node (ref "R10") (pin "2") (pinfunction "2_2") (pintype "passive"))
      (node (ref "R9") (pin "2") (pinfunction "2_2") (pintype "passive"))
      (node (ref "U3") (pin "3") (pinfunction "EN_3") (pintype "input"))
    )
    (net (code "45") (name "Net-(D2-A)") (class "Default")
      (node (ref "D2") (pin "2") (pinfunction "A_2") (pintype "passive"))
      (node (ref "P6") (pin "1") (pinfunction "1_1") (pintype "passive"))
      (node (ref "T3") (pin "3") (pinfunction "D_3") (pintype "passive"))
    )
    (net (code "46") (name "Net-(R5-Pad1)") (class "Default")
      (node (ref "R5") (pin "1") (pinfunction "1_1") (pintype "passive"))
      (node (ref "T2") (pin "1") (pinfunction "B_1") (pintype "passive"))
      (node (ref "T2") (pin "2") (pinfunction "C_2") (pintype "passive"))
      (node (ref "T2") (pin "3") (pinfunction "B_3") (pintype "passive"))
    )
    (net (code "47") (name "Net-(T1-G)") (class "Default")
      (node (ref "R6") (pin "1") (pinfunction "1_1") (pintype "passive"))
      (node (ref "T1") (pin "1") (pinfunction "G_1") (pintype "passive"))
      (node (ref "T2") (pin "4") (pinfunction "C_4") (pintype "passive"))
    )
    (net (code "48") (name "Net-(T3-G)") (class "Default")
      (node (ref "R16") (pin "1") (pinfunction "1_1") (pintype "passive"))
      (node (ref "R17") (pin "1") (pinfunction "1_1") (pintype "passive"))
      (node (ref "T3") (pin "1") (pinfunction "G_1") (pintype "passive"))
    )
    (net (code "49") (name "Net-(U2-BSTRPA+)") (class "Default")
      (node (ref "C22") (pin "2") (pinfunction "2_2") (pintype "passive"))
      (node (ref "U2") (pin "5") (pinfunction "BSTRPA+_5") (pintype "passive"))
    )
    (net (code "50") (name "Net-(U2-BSTRPA-)") (class "Default")
      (node (ref "C17") (pin "2") (pinfunction "2_2") (pintype "passive"))
      (node (ref "U2") (pin "1") (pinfunction "BSTRPA-_1") (pintype "passive"))
    )
    (net (code "51") (name "Net-(U2-BSTRPB+)") (class "Default")
      (node (ref "C24") (pin "2") (pinfunction "2_2") (pintype "passive"))
      (node (ref "U2") (pin "44") (pinfunction "BSTRPB+_44") (pintype "passive"))
    )
    (net (code "52") (name "Net-(U2-BSTRPB-)") (class "Default")
      (node (ref "C23") (pin "2") (pinfunction "2_2") (pintype "passive"))
      (node (ref "U2") (pin "48") (pinfunction "BSTRPB-_48") (pintype "passive"))
    )
    (net (code "53") (name "Net-(U2-CN)") (class "Default")
      (node (ref "C12") (pin "2") (pinfunction "2_2") (pintype "passive"))
      (node (ref "U2") (pin "34") (pinfunction "CN_34") (pintype "passive"))
    )
    (net (code "54") (name "Net-(U2-CP)") (class "Default")
      (node (ref "C12") (pin "1") (pinfunction "1_1") (pintype "passive"))
      (node (ref "U2") (pin "32") (pinfunction "CP_32") (pintype "passive"))
    )
    (net (code "55") (name "Net-(U2-CPVSS)") (class "Default")
      (node (ref "C13") (pin "1") (pinfunction "1_1") (pintype "passive"))
      (node (ref "U2") (pin "35") (pinfunction "CPVSS_35") (pintype "passive"))
    )
    (net (code "56") (name "Net-(U2-DAC_OUTA)") (class "Default")
      (node (ref "C14") (pin "1") (pinfunction "1_1") (pintype "passive"))
      (node (ref "U2") (pin "13") (pinfunction "DAC_OUTA_13") (pintype "passive"))
    )
    (net (code "57") (name "Net-(U2-DAC_OUTB)") (class "Default")
      (node (ref "C18") (pin "1") (pinfunction "1_1") (pintype "passive"))
      (node (ref "U2") (pin "36") (pinfunction "DAC_OUTB_36") (pintype "passive"))
    )
    (net (code "58") (name "Net-(U2-DVDD_REG)") (class "Default")
      (node (ref "C16") (pin "1") (pinfunction "1_1") (pintype "passive"))
      (node (ref "U2") (pin "28") (pinfunction "DVDD_REG_28") (pintype "power_in"))
    )
    (net (code "59") (name "Net-(U2-GVDD_REG)") (class "Default")
      (node (ref "C2") (pin "1") (pinfunction "1_1") (pintype "passive"))
      (node (ref "R4") (pin "2") (pinfunction "2_2") (pintype "passive"))
      (node (ref "U2") (pin "8") (pinfunction "GVDD_REG_8") (pintype "power_in"))
    )
    (net (code "60") (name "Net-(U2-SPK_GAIN{slash}FREQ)") (class "Default")
      (node (ref "R13") (pin "2") (pinfunction "2_2") (pintype "passive"))
      (node (ref "R4") (pin "1") (pinfunction "1_1") (pintype "passive"))
      (node (ref "U2") (pin "9") (pinfunction "SPK_GAIN/FREQ_9") (pintype "passive"))
    )
    (net (code "61") (name "Net-(U2-SPK_INA+)") (class "Default")
      (node (ref "C14") (pin "2") (pinfunction "2_2") (pintype "passive"))
      (node (ref "U2") (pin "12") (pinfunction "SPK_INA+_12") (pintype "passive"))
    )
    (net (code "62") (name "Net-(U2-SPK_INA-)") (class "Default")
      (node (ref "C15") (pin "2") (pinfunction "2_2") (pintype "passive"))
      (node (ref "U2") (pin "11") (pinfunction "SPK_INA-_11") (pintype "passive"))
    )
    (net (code "63") (name "Net-(U2-SPK_INB+)") (class "Default")
      (node (ref "C18") (pin "2") (pinfunction "2_2") (pintype "passive"))
      (node (ref "U2") (pin "37") (pinfunction "SPK_INB+_37") (pintype "passive"))
    )
    (net (code "64") (name "Net-(U2-SPK_INB-)") (class "Default")
      (node (ref "C19") (pin "2") (pinfunction "2_2") (pintype "passive"))
      (node (ref "U2") (pin "38") (pinfunction "SPK_INB-_38") (pintype "passive"))
    )
    (net (code "65") (name "Net-(U2-SPK_OUTA+)") (class "Default")
      (node (ref "C22") (pin "1") (pinfunction "1_1") (pintype "passive"))
      (node (ref "L3") (pin "1") (pinfunction "1_1") (pintype "passive"))
      (node (ref "U2") (pin "4") (pinfunction "SPK_OUTA+_4") (pintype "passive"))
    )
    (net (code "66") (name "Net-(U2-SPK_OUTA-)") (class "Default")
      (node (ref "C17") (pin "1") (pinfunction "1_1") (pintype "passive"))
      (node (ref "L4") (pin "1") (pinfunction "1_1") (pintype "passive"))
      (node (ref "U2") (pin "2") (pinfunction "SPK_OUTA-_2") (pintype "passive"))
    )
    (net (code "67") (name "Net-(U2-SPK_OUTB+)") (class "Default")
      (node (ref "C24") (pin "1") (pinfunction "1_1") (pintype "passive"))
      (node (ref "L2") (pin "1") (pinfunction "1_1") (pintype "passive"))
      (node (ref "U2") (pin "45") (pinfunction "SPK_OUTB+_45") (pintype "passive"))
    )
    (net (code "68") (name "Net-(U2-SPK_OUTB-)") (class "Default")
      (node (ref "C23") (pin "1") (pinfunction "1_1") (pintype "passive"))
      (node (ref "L1") (pin "1") (pinfunction "1_1") (pintype "passive"))
      (node (ref "U2") (pin "47") (pinfunction "SPK_OUTB-_47") (pintype "passive"))
    )
    (net (code "69") (name "Net-(U3-FB)") (class "Default")
      (node (ref "R7") (pin "2") (pinfunction "2_2") (pintype "passive"))
      (node (ref "R8") (pin "1") (pinfunction "1_1") (pintype "passive"))
      (node (ref "U3") (pin "5") (pinfunction "FB_5") (pintype "input"))
    )
    (net (code "70") (name "Net-(U3-SS{slash}TRK)") (class "Default")
      (node (ref "C29") (pin "2") (pinfunction "2_2") (pintype "passive"))
      (node (ref "U3") (pin "6") (pinfunction "SS/TRK_6") (pintype "power_in"))
    )
    (net (code "71") (name "Net-(U4-ALERT)") (class "Default")
      (node (ref "R14") (pin "2") (pinfunction "2_2") (pintype "passive"))
      (node (ref "R15") (pin "2") (pinfunction "2_2") (pintype "passive"))
      (node (ref "R16") (pin "2") (pinfunction "2_2") (pintype "passive"))
      (node (ref "U4") (pin "3") (pinfunction "ALERT_3") (pintype "output"))
    )
    (net (code "72") (name "PVDD") (class "Default")
      (node (ref "C20") (pin "1") (pinfunction "1_1") (pintype "passive"))
      (node (ref "C21") (pin "1") (pinfunction "1_1") (pintype "passive"))
      (node (ref "C3") (pin "1") (pinfunction "1_1") (pintype "passive"))
      (node (ref "C32") (pin "1") (pinfunction "1_1") (pintype "passive"))
      (node (ref "C33") (pin "1") (pinfunction "1_1") (pintype "passive"))
      (node (ref "C34") (pin "1") (pinfunction "1_1") (pintype "passive"))
      (node (ref "C35") (pin "1") (pinfunction "1_1") (pintype "passive"))
      (node (ref "C4") (pin "1") (pinfunction "1_1") (pintype "passive"))
      (node (ref "C5") (pin "1") (pinfunction "1_1") (pintype "passive"))
      (node (ref "C6") (pin "1") (pinfunction "1_1") (pintype "passive"))
      (node (ref "C7") (pin "1") (pinfunction "1_1") (pintype "passive"))
      (node (ref "C8") (pin "1") (pinfunction "1_1") (pintype "passive"))
      (node (ref "D2") (pin "1") (pinfunction "C_1") (pintype "passive"))
      (node (ref "P3") (pin "1") (pinfunction "1_1") (pintype "passive"))
      (node (ref "P6") (pin "2") (pinfunction "2_2") (pintype "passive"))
      (node (ref "R9") (pin "1") (pinfunction "1_1") (pintype "passive"))
      (node (ref "U2") (pin "41") (pinfunction "PVDD_41") (pintype "power_in"))
      (node (ref "U2") (pin "42") (pinfunction "PVDD_42") (pintype "power_in"))
      (node (ref "U2") (pin "43") (pinfunction "PVDD_43") (pintype "power_in"))
      (node (ref "U2") (pin "6") (pinfunction "PVDD_6") (pintype "power_in"))
      (node (ref "U2") (pin "7") (pinfunction "PVDD_7") (pintype "power_in"))
      (node (ref "U3") (pin "1") (pinfunction "VIN_1") (pintype "power_in"))
    )
  )
)
